# carbsync.net
KiCad netlist of a schematic drawn in EAGLE
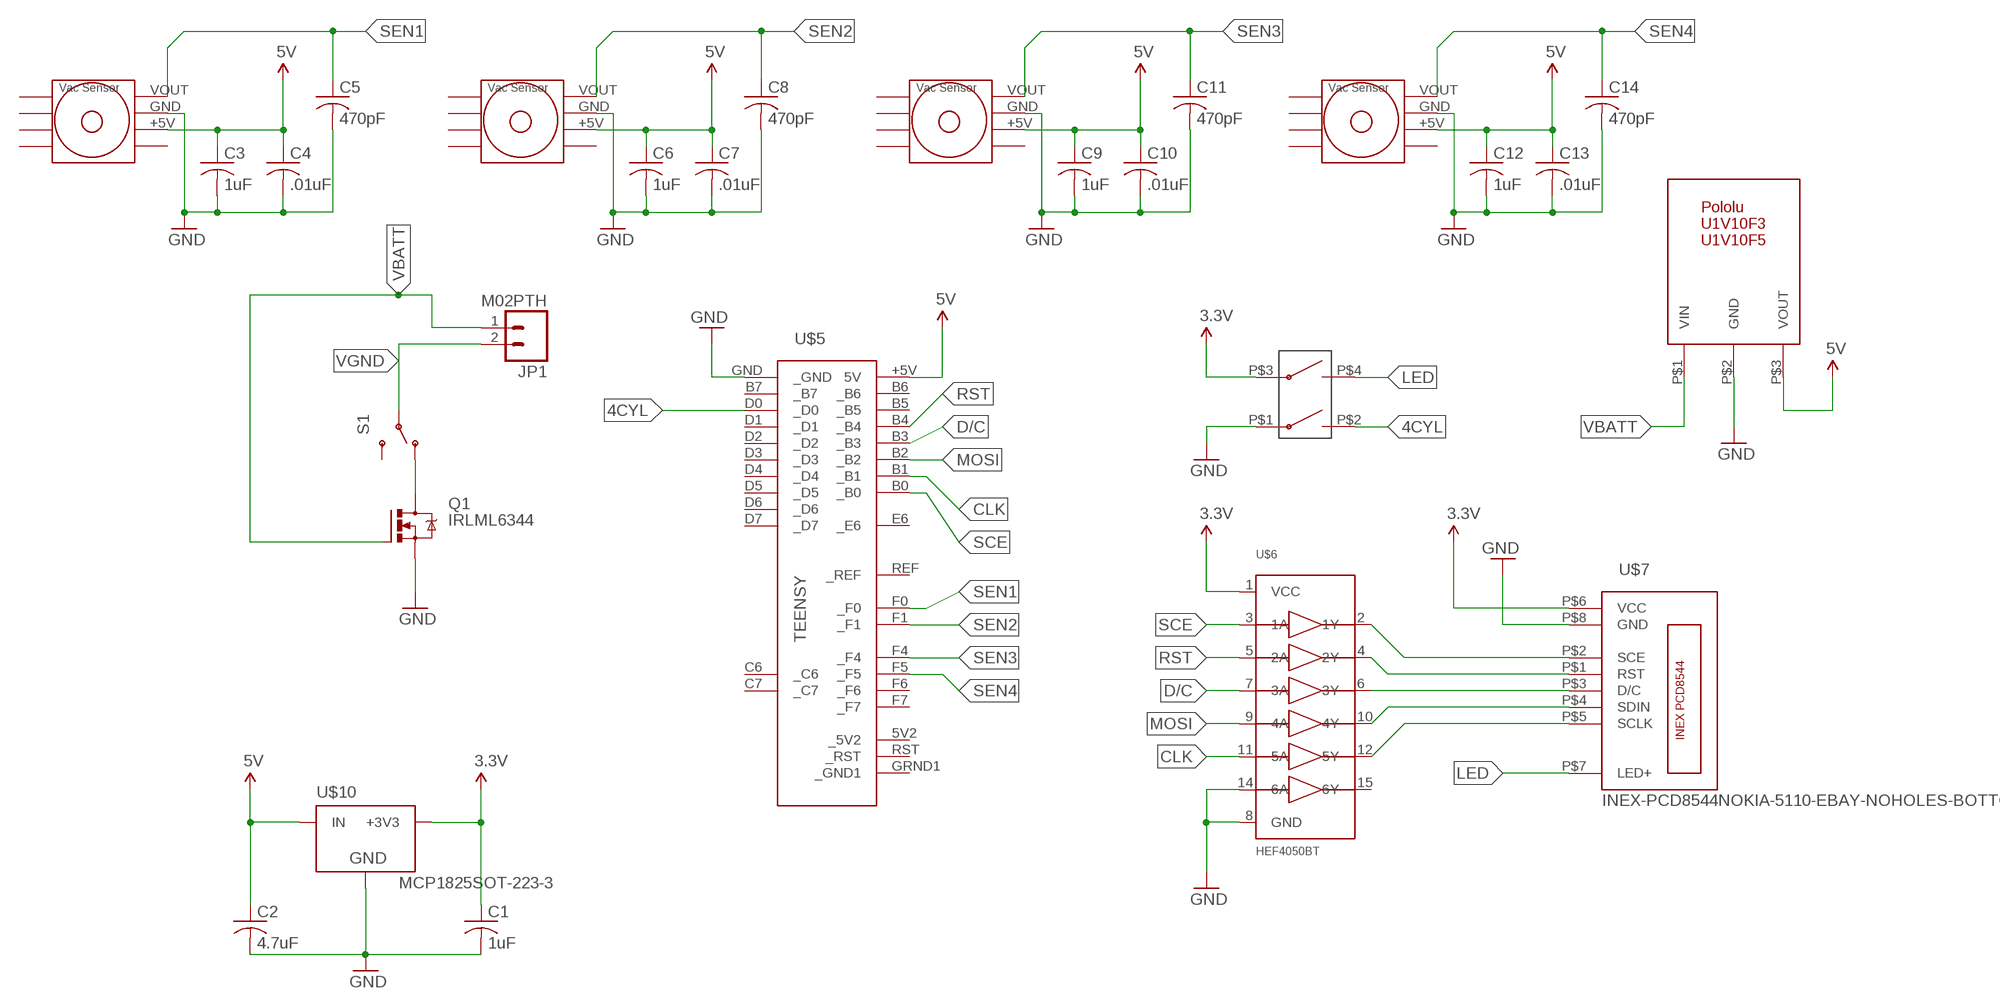
[diagram p0: schematic, sheet 1]

(export (version "E")
  (design (tool "Eeschema 10.0.6"))
  (components
    (comp (ref "C1")
      (value "1uF")
      (footprint "eagle-import:C0805")
      (libsource (lib "eagle-import") (part "C-USC0805"))
    )
    (comp (ref "C2")
      (value "4.7uF")
      (footprint "eagle-import:C0805")
      (libsource (lib "eagle-import") (part "C-USC0805"))
    )
    (comp (ref "C3")
      (value "1uF")
      (footprint "eagle-import:C0805")
      (libsource (lib "eagle-import") (part "C-USC0805"))
    )
    (comp (ref "C4")
      (value ".01uF")
      (footprint "eagle-import:C0805")
      (libsource (lib "eagle-import") (part "C-USC0805"))
    )
    (comp (ref "C5")
      (value "470pF")
      (footprint "eagle-import:C0603")
      (libsource (lib "eagle-import") (part "C-USC0603"))
    )
    (comp (ref "C6")
      (value "1uF")
      (footprint "eagle-import:C0805")
      (libsource (lib "eagle-import") (part "C-USC0805"))
    )
    (comp (ref "C7")
      (value ".01uF")
      (footprint "eagle-import:C0805")
      (libsource (lib "eagle-import") (part "C-USC0805"))
    )
    (comp (ref "C8")
      (value "470pF")
      (footprint "eagle-import:C0603")
      (libsource (lib "eagle-import") (part "C-USC0603"))
    )
    (comp (ref "C9")
      (value "1uF")
      (footprint "eagle-import:C0805")
      (libsource (lib "eagle-import") (part "C-USC0805"))
    )
    (comp (ref "C10")
      (value ".01uF")
      (footprint "eagle-import:C0805")
      (libsource (lib "eagle-import") (part "C-USC0805"))
    )
    (comp (ref "C11")
      (value "470pF")
      (footprint "eagle-import:C0603")
      (libsource (lib "eagle-import") (part "C-USC0603"))
    )
    (comp (ref "C12")
      (value "1uF")
      (footprint "eagle-import:C0805")
      (libsource (lib "eagle-import") (part "C-USC0805"))
    )
    (comp (ref "C13")
      (value ".01uF")
      (footprint "eagle-import:C0805")
      (libsource (lib "eagle-import") (part "C-USC0805"))
    )
    (comp (ref "C14")
      (value "470pF")
      (footprint "eagle-import:C0603")
      (libsource (lib "eagle-import") (part "C-USC0603"))
    )
    (comp (ref "JP1")
      (value "M02PTH")
      (footprint "eagle-import:1X02")
      (libsource (lib "eagle-import") (part "M02PTH"))
    )
    (comp (ref "Q1")
      (value "IRLML6344")
      (footprint "eagle-import:SOT23")
      (libsource (lib "eagle-import") (part "IRLML6344"))
    )
    (comp (ref "S1")
      (value "SWITCH-SPDT")
      (footprint "eagle-import:CWI286-SPDT-NOTABS")
      (libsource (lib "eagle-import") (part "SWITCH-SPDT"))
    )
    (comp (ref "U$1")
      (value "MPXV5050V")
      (footprint "eagle-import:MPXV5050V")
      (libsource (lib "eagle-import") (part "MPXV5050V"))
    )
    (comp (ref "U$2")
      (value "MPXV5050V")
      (footprint "eagle-import:MPXV5050V")
      (libsource (lib "eagle-import") (part "MPXV5050V"))
    )
    (comp (ref "U$3")
      (value "MPXV5050V")
      (footprint "eagle-import:MPXV5050V")
      (libsource (lib "eagle-import") (part "MPXV5050V"))
    )
    (comp (ref "U$4")
      (value "MPXV5050V")
      (footprint "eagle-import:MPXV5050V")
      (libsource (lib "eagle-import") (part "MPXV5050V"))
    )
    (comp (ref "U$5")
      (value "TEENSY")
      (footprint "eagle-import:TEENSY")
      (libsource (lib "eagle-import") (part "TEENSY"))
    )
    (comp (ref "U$6")
      (value "HEF4050BT")
      (footprint "eagle-import:SOIC16")
      (libsource (lib "eagle-import") (part "74HC4050D"))
    )
    (comp (ref "U$7")
      (value "INEX-PCD8544NOKIA-5110-EBAY-NOHOLES-BOTTOM")
      (footprint "eagle-import:NOKIA-5110-EBAY-NOHOLES")
      (libsource (lib "eagle-import") (part "INEX-PCD8544NOKIA-5110-EBAY-NOHOLES-BOTTOM"))
    )
    (comp (ref "U$8")
      (value "POLOLU-DC-3PINU1V10F5-5V-DC-UP")
      (footprint "eagle-import:POLOLU-DC-3PIN")
      (libsource (lib "eagle-import") (part "POLOLU-DC-3PINU1V10F5-5V-DC-UP"))
    )
    (comp (ref "U$9")
      (value "CT-219-X-MST")
      (footprint "eagle-import:CT219-2-MST")
      (libsource (lib "eagle-import") (part "CT-219-X-MST"))
    )
    (comp (ref "U$10")
      (value "MCP1825SOT-223-3")
      (footprint "eagle-import:SOT-223")
      (libsource (lib "eagle-import") (part "MCP1825SOT-223-3"))
    )
  )
  (nets
    (net (code "1") (name "3.3V") (class "Default")
      (node (ref "C1") (pin "1") (pinfunction "1_1") (pintype "passive"))
      (node (ref "U$10") (pin "3") (pinfunction "+3V3_3") (pintype "power_in"))
      (node (ref "U$6") (pin "1") (pinfunction "VCC_1") (pintype "bidirectional"))
      (node (ref "U$7") (pin "P$6") (pinfunction "VCC_P$6") (pintype "power_in"))
      (node (ref "U$9") (pin "P$3") (pinfunction "P$3_P$3") (pintype "bidirectional"))
    )
    (net (code "2") (name "4CYL") (class "Default")
      (node (ref "U$5") (pin "D0") (pinfunction "_D0_D0") (pintype "bidirectional"))
      (node (ref "U$9") (pin "P$2") (pinfunction "P$2_P$2") (pintype "bidirectional"))
    )
    (net (code "3") (name "5V") (class "Default")
      (node (ref "C10") (pin "1") (pinfunction "1_1") (pintype "passive"))
      (node (ref "C12") (pin "1") (pinfunction "1_1") (pintype "passive"))
      (node (ref "C13") (pin "1") (pinfunction "1_1") (pintype "passive"))
      (node (ref "C2") (pin "1") (pinfunction "1_1") (pintype "passive"))
      (node (ref "C3") (pin "1") (pinfunction "1_1") (pintype "passive"))
      (node (ref "C4") (pin "1") (pinfunction "1_1") (pintype "passive"))
      (node (ref "C6") (pin "1") (pinfunction "1_1") (pintype "passive"))
      (node (ref "C7") (pin "1") (pinfunction "1_1") (pintype "passive"))
      (node (ref "C9") (pin "1") (pinfunction "1_1") (pintype "passive"))
      (node (ref "U$1") (pin "+5V") (pinfunction "5V_+5V") (pintype "power_in"))
      (node (ref "U$10") (pin "1") (pinfunction "IN_1") (pintype "power_in"))
      (node (ref "U$2") (pin "+5V") (pinfunction "5V_+5V") (pintype "power_in"))
      (node (ref "U$3") (pin "+5V") (pinfunction "5V_+5V") (pintype "power_in"))
      (node (ref "U$4") (pin "+5V") (pinfunction "5V_+5V") (pintype "power_in"))
      (node (ref "U$5") (pin "+5V") (pinfunction "5V_+5V") (pintype "bidirectional"))
      (node (ref "U$8") (pin "P$3") (pinfunction "VOUT_P$3") (pintype "power_in"))
    )
    (net (code "4") (name "CLK") (class "Default")
      (node (ref "U$5") (pin "B1") (pinfunction "_B1_B1") (pintype "bidirectional"))
      (node (ref "U$6") (pin "11") (pinfunction "5A_11") (pintype "bidirectional"))
    )
    (net (code "5") (name "D{slash}C") (class "Default")
      (node (ref "U$5") (pin "B3") (pinfunction "_B3_B3") (pintype "bidirectional"))
      (node (ref "U$6") (pin "7") (pinfunction "3A_7") (pintype "bidirectional"))
    )
    (net (code "6") (name "GND") (class "Default")
      (node (ref "C1") (pin "2") (pinfunction "2_2") (pintype "passive"))
      (node (ref "C10") (pin "2") (pinfunction "2_2") (pintype "passive"))
      (node (ref "C11") (pin "2") (pinfunction "2_2") (pintype "passive"))
      (node (ref "C12") (pin "2") (pinfunction "2_2") (pintype "passive"))
      (node (ref "C13") (pin "2") (pinfunction "2_2") (pintype "passive"))
      (node (ref "C14") (pin "2") (pinfunction "2_2") (pintype "passive"))
      (node (ref "C2") (pin "2") (pinfunction "2_2") (pintype "passive"))
      (node (ref "C3") (pin "2") (pinfunction "2_2") (pintype "passive"))
      (node (ref "C4") (pin "2") (pinfunction "2_2") (pintype "passive"))
      (node (ref "C5") (pin "2") (pinfunction "2_2") (pintype "passive"))
      (node (ref "C6") (pin "2") (pinfunction "2_2") (pintype "passive"))
      (node (ref "C7") (pin "2") (pinfunction "2_2") (pintype "passive"))
      (node (ref "C8") (pin "2") (pinfunction "2_2") (pintype "passive"))
      (node (ref "C9") (pin "2") (pinfunction "2_2") (pintype "passive"))
      (node (ref "Q1") (pin "2") (pinfunction "S_2") (pintype "passive"))
      (node (ref "U$1") (pin "GND") (pinfunction "GND_GND") (pintype "power_in"))
      (node (ref "U$10") (pin "2") (pinfunction "GND_2") (pintype "power_in"))
      (node (ref "U$10") (pin "4") (pinfunction "GND_4") (pintype "power_in"))
      (node (ref "U$2") (pin "GND") (pinfunction "GND_GND") (pintype "power_in"))
      (node (ref "U$3") (pin "GND") (pinfunction "GND_GND") (pintype "power_in"))
      (node (ref "U$4") (pin "GND") (pinfunction "GND_GND") (pintype "power_in"))
      (node (ref "U$5") (pin "GND") (pinfunction "_GND_GND") (pintype "bidirectional"))
      (node (ref "U$6") (pin "14") (pinfunction "6A_14") (pintype "bidirectional"))
      (node (ref "U$6") (pin "8") (pinfunction "GND_8") (pintype "bidirectional"))
      (node (ref "U$7") (pin "P$8") (pinfunction "GND_P$8") (pintype "power_in"))
      (node (ref "U$8") (pin "P$2") (pinfunction "GND_P$2") (pintype "power_in"))
      (node (ref "U$9") (pin "P$1") (pinfunction "P$1_P$1") (pintype "bidirectional"))
    )
    (net (code "7") (name "LED") (class "Default")
      (node (ref "U$7") (pin "P$7") (pinfunction "LED+_P$7") (pintype "power_in"))
      (node (ref "U$9") (pin "P$4") (pinfunction "P$4_P$4") (pintype "bidirectional"))
    )
    (net (code "8") (name "MOSI") (class "Default")
      (node (ref "U$5") (pin "B2") (pinfunction "_B2_B2") (pintype "bidirectional"))
      (node (ref "U$6") (pin "9") (pinfunction "4A_9") (pintype "bidirectional"))
    )
    (net (code "9") (name "Net-(Q1-D)") (class "Default")
      (node (ref "Q1") (pin "3") (pinfunction "D_3") (pintype "passive"))
      (node (ref "S1") (pin "P$1") (pinfunction "O_P$1") (pintype "passive"))
    )
    (net (code "10") (name "Net-(U$6-1Y)") (class "Default")
      (node (ref "U$6") (pin "2") (pinfunction "1Y_2") (pintype "bidirectional"))
      (node (ref "U$7") (pin "P$2") (pinfunction "SCE_P$2") (pintype "input"))
    )
    (net (code "11") (name "Net-(U$6-2Y)") (class "Default")
      (node (ref "U$6") (pin "4") (pinfunction "2Y_4") (pintype "bidirectional"))
      (node (ref "U$7") (pin "P$1") (pinfunction "RST_P$1") (pintype "input"))
    )
    (net (code "12") (name "Net-(U$6-3Y)") (class "Default")
      (node (ref "U$6") (pin "6") (pinfunction "3Y_6") (pintype "bidirectional"))
      (node (ref "U$7") (pin "P$3") (pinfunction "D/C_P$3") (pintype "input"))
    )
    (net (code "13") (name "Net-(U$6-4Y)") (class "Default")
      (node (ref "U$6") (pin "10") (pinfunction "4Y_10") (pintype "bidirectional"))
      (node (ref "U$7") (pin "P$4") (pinfunction "SDIN_P$4") (pintype "input"))
    )
    (net (code "14") (name "Net-(U$6-5Y)") (class "Default")
      (node (ref "U$6") (pin "12") (pinfunction "5Y_12") (pintype "bidirectional"))
      (node (ref "U$7") (pin "P$5") (pinfunction "SCLK_P$5") (pintype "input"))
    )
    (net (code "15") (name "RST") (class "Default")
      (node (ref "U$5") (pin "B4") (pinfunction "_B4_B4") (pintype "bidirectional"))
      (node (ref "U$6") (pin "5") (pinfunction "2A_5") (pintype "bidirectional"))
    )
    (net (code "16") (name "SCE") (class "Default")
      (node (ref "U$5") (pin "B0") (pinfunction "_B0_B0") (pintype "bidirectional"))
      (node (ref "U$6") (pin "3") (pinfunction "1A_3") (pintype "bidirectional"))
    )
    (net (code "17") (name "SEN1") (class "Default")
      (node (ref "C5") (pin "1") (pinfunction "1_1") (pintype "passive"))
      (node (ref "U$1") (pin "VOUT") (pinfunction "VOUT_VOUT") (pintype "output"))
      (node (ref "U$5") (pin "F0") (pinfunction "_F0_F0") (pintype "bidirectional"))
    )
    (net (code "18") (name "SEN2") (class "Default")
      (node (ref "C8") (pin "1") (pinfunction "1_1") (pintype "passive"))
      (node (ref "U$2") (pin "VOUT") (pinfunction "VOUT_VOUT") (pintype "output"))
      (node (ref "U$5") (pin "F1") (pinfunction "_F1_F1") (pintype "bidirectional"))
    )
    (net (code "19") (name "SEN3") (class "Default")
      (node (ref "C11") (pin "1") (pinfunction "1_1") (pintype "passive"))
      (node (ref "U$3") (pin "VOUT") (pinfunction "VOUT_VOUT") (pintype "output"))
      (node (ref "U$5") (pin "F4") (pinfunction "_F4_F4") (pintype "bidirectional"))
    )
    (net (code "20") (name "SEN4") (class "Default")
      (node (ref "C14") (pin "1") (pinfunction "1_1") (pintype "passive"))
      (node (ref "U$4") (pin "VOUT") (pinfunction "VOUT_VOUT") (pintype "output"))
      (node (ref "U$5") (pin "F5") (pinfunction "_F5_F5") (pintype "bidirectional"))
    )
    (net (code "21") (name "VBATT") (class "Default")
      (node (ref "JP1") (pin "1") (pinfunction "1_1") (pintype "passive"))
      (node (ref "Q1") (pin "1") (pinfunction "G_1") (pintype "passive"))
      (node (ref "U$8") (pin "P$1") (pinfunction "VIN_P$1") (pintype "power_in"))
    )
    (net (code "22") (name "VGND") (class "Default")
      (node (ref "JP1") (pin "2") (pinfunction "2_2") (pintype "passive"))
      (node (ref "S1") (pin "P$2") (pinfunction "P_P$2") (pintype "passive"))
    )
    (net (code "23") (name "unconnected-(S1-S-PadP$3)") (class "Default")
      (node (ref "S1") (pin "P$3") (pinfunction "S_P$3") (pintype "passive"))
    )
    (net (code "24") (name "unconnected-(U$1-PadP$1)") (class "Default")
      (node (ref "U$1") (pin "P$1") (pinfunction "P$1_P$1") (pintype "no_connect"))
    )
    (net (code "25") (name "unconnected-(U$1-PadP$5)") (class "Default")
      (node (ref "U$1") (pin "P$5") (pinfunction "P$5_P$5") (pintype "no_connect"))
    )
    (net (code "26") (name "unconnected-(U$1-PadP$6)") (class "Default")
      (node (ref "U$1") (pin "P$6") (pinfunction "P$6_P$6") (pintype "no_connect"))
    )
    (net (code "27") (name "unconnected-(U$1-PadP$7)") (class "Default")
      (node (ref "U$1") (pin "P$7") (pinfunction "P$7_P$7") (pintype "no_connect"))
    )
    (net (code "28") (name "unconnected-(U$1-PadP$8)") (class "Default")
      (node (ref "U$1") (pin "P$8") (pinfunction "P$8_P$8") (pintype "no_connect"))
    )
    (net (code "29") (name "unconnected-(U$2-PadP$1)") (class "Default")
      (node (ref "U$2") (pin "P$1") (pinfunction "P$1_P$1") (pintype "no_connect"))
    )
    (net (code "30") (name "unconnected-(U$2-PadP$5)") (class "Default")
      (node (ref "U$2") (pin "P$5") (pinfunction "P$5_P$5") (pintype "no_connect"))
    )
    (net (code "31") (name "unconnected-(U$2-PadP$6)") (class "Default")
      (node (ref "U$2") (pin "P$6") (pinfunction "P$6_P$6") (pintype "no_connect"))
    )
    (net (code "32") (name "unconnected-(U$2-PadP$7)") (class "Default")
      (node (ref "U$2") (pin "P$7") (pinfunction "P$7_P$7") (pintype "no_connect"))
    )
    (net (code "33") (name "unconnected-(U$2-PadP$8)") (class "Default")
      (node (ref "U$2") (pin "P$8") (pinfunction "P$8_P$8") (pintype "no_connect"))
    )
    (net (code "34") (name "unconnected-(U$3-PadP$1)") (class "Default")
      (node (ref "U$3") (pin "P$1") (pinfunction "P$1_P$1") (pintype "no_connect"))
    )
    (net (code "35") (name "unconnected-(U$3-PadP$5)") (class "Default")
      (node (ref "U$3") (pin "P$5") (pinfunction "P$5_P$5") (pintype "no_connect"))
    )
    (net (code "36") (name "unconnected-(U$3-PadP$6)") (class "Default")
      (node (ref "U$3") (pin "P$6") (pinfunction "P$6_P$6") (pintype "no_connect"))
    )
    (net (code "37") (name "unconnected-(U$3-PadP$7)") (class "Default")
      (node (ref "U$3") (pin "P$7") (pinfunction "P$7_P$7") (pintype "no_connect"))
    )
    (net (code "38") (name "unconnected-(U$3-PadP$8)") (class "Default")
      (node (ref "U$3") (pin "P$8") (pinfunction "P$8_P$8") (pintype "no_connect"))
    )
    (net (code "39") (name "unconnected-(U$4-PadP$1)") (class "Default")
      (node (ref "U$4") (pin "P$1") (pinfunction "P$1_P$1") (pintype "no_connect"))
    )
    (net (code "40") (name "unconnected-(U$4-PadP$5)") (class "Default")
      (node (ref "U$4") (pin "P$5") (pinfunction "P$5_P$5") (pintype "no_connect"))
    )
    (net (code "41") (name "unconnected-(U$4-PadP$6)") (class "Default")
      (node (ref "U$4") (pin "P$6") (pinfunction "P$6_P$6") (pintype "no_connect"))
    )
    (net (code "42") (name "unconnected-(U$4-PadP$7)") (class "Default")
      (node (ref "U$4") (pin "P$7") (pinfunction "P$7_P$7") (pintype "no_connect"))
    )
    (net (code "43") (name "unconnected-(U$4-PadP$8)") (class "Default")
      (node (ref "U$4") (pin "P$8") (pinfunction "P$8_P$8") (pintype "no_connect"))
    )
    (net (code "44") (name "unconnected-(U$5-_5V2-Pad5V2)") (class "Default")
      (node (ref "U$5") (pin "5V2") (pinfunction "_5V2_5V2") (pintype "bidirectional"))
    )
    (net (code "45") (name "unconnected-(U$5-_B5-PadB5)") (class "Default")
      (node (ref "U$5") (pin "B5") (pinfunction "_B5_B5") (pintype "bidirectional"))
    )
    (net (code "46") (name "unconnected-(U$5-_B6-PadB6)") (class "Default")
      (node (ref "U$5") (pin "B6") (pinfunction "_B6_B6") (pintype "bidirectional"))
    )
    (net (code "47") (name "unconnected-(U$5-_B7-PadB7)") (class "Default")
      (node (ref "U$5") (pin "B7") (pinfunction "_B7_B7") (pintype "bidirectional"))
    )
    (net (code "48") (name "unconnected-(U$5-_C6-PadC6)") (class "Default")
      (node (ref "U$5") (pin "C6") (pinfunction "_C6_C6") (pintype "bidirectional"))
    )
    (net (code "49") (name "unconnected-(U$5-_C7-PadC7)") (class "Default")
      (node (ref "U$5") (pin "C7") (pinfunction "_C7_C7") (pintype "bidirectional"))
    )
    (net (code "50") (name "unconnected-(U$5-_D1-PadD1)") (class "Default")
      (node (ref "U$5") (pin "D1") (pinfunction "_D1_D1") (pintype "bidirectional"))
    )
    (net (code "51") (name "unconnected-(U$5-_D2-PadD2)") (class "Default")
      (node (ref "U$5") (pin "D2") (pinfunction "_D2_D2") (pintype "bidirectional"))
    )
    (net (code "52") (name "unconnected-(U$5-_D3-PadD3)") (class "Default")
      (node (ref "U$5") (pin "D3") (pinfunction "_D3_D3") (pintype "bidirectional"))
    )
    (net (code "53") (name "unconnected-(U$5-_D4-PadD4)") (class "Default")
      (node (ref "U$5") (pin "D4") (pinfunction "_D4_D4") (pintype "bidirectional"))
    )
    (net (code "54") (name "unconnected-(U$5-_D5-PadD5)") (class "Default")
      (node (ref "U$5") (pin "D5") (pinfunction "_D5_D5") (pintype "bidirectional"))
    )
    (net (code "55") (name "unconnected-(U$5-_D6-PadD6)") (class "Default")
      (node (ref "U$5") (pin "D6") (pinfunction "_D6_D6") (pintype "bidirectional"))
    )
    (net (code "56") (name "unconnected-(U$5-_D7-PadD7)") (class "Default")
      (node (ref "U$5") (pin "D7") (pinfunction "_D7_D7") (pintype "bidirectional"))
    )
    (net (code "57") (name "unconnected-(U$5-_E6-PadE6)") (class "Default")
      (node (ref "U$5") (pin "E6") (pinfunction "_E6_E6") (pintype "bidirectional"))
    )
    (net (code "58") (name "unconnected-(U$5-_F6-PadF6)") (class "Default")
      (node (ref "U$5") (pin "F6") (pinfunction "_F6_F6") (pintype "bidirectional"))
    )
    (net (code "59") (name "unconnected-(U$5-_F7-PadF7)") (class "Default")
      (node (ref "U$5") (pin "F7") (pinfunction "_F7_F7") (pintype "bidirectional"))
    )
    (net (code "60") (name "unconnected-(U$5-_GND1-PadGRND1)") (class "Default")
      (node (ref "U$5") (pin "GRND1") (pinfunction "_GND1_GRND1") (pintype "bidirectional"))
    )
    (net (code "61") (name "unconnected-(U$5-_REF-PadREF)") (class "Default")
      (node (ref "U$5") (pin "REF") (pinfunction "_REF_REF") (pintype "bidirectional"))
    )
    (net (code "62") (name "unconnected-(U$5-_RST-PadRST)") (class "Default")
      (node (ref "U$5") (pin "RST") (pinfunction "_RST_RST") (pintype "bidirectional"))
    )
    (net (code "63") (name "unconnected-(U$6-6Y-Pad15)") (class "Default")
      (node (ref "U$6") (pin "15") (pinfunction "6Y_15") (pintype "bidirectional"))
    )
  )
)
